# RS232-TTL.net
KiCad netlist of a schematic drawn in EAGLE
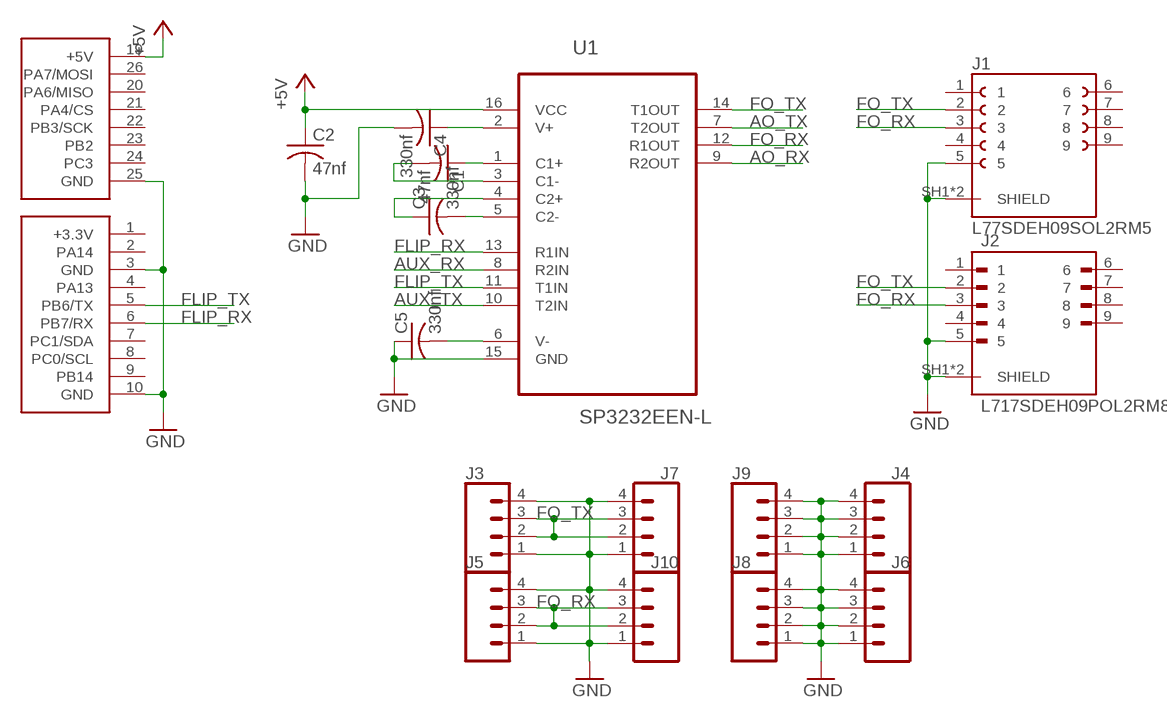
[diagram p0: schematic, sheet 1]

(export (version "E")
  (design (tool "Eeschema 10.0.6"))
  (components
    (comp (ref "C1")
      (value "47nf")
      (footprint "eagle-import:C0805")
      (libsource (lib "eagle-import") (part "C-USC0805"))
    )
    (comp (ref "C2")
      (value "47nf")
      (footprint "eagle-import:C0805")
      (libsource (lib "eagle-import") (part "C-USC0805"))
    )
    (comp (ref "C3")
      (value "330nf")
      (footprint "eagle-import:C0805")
      (libsource (lib "eagle-import") (part "C-USC0805"))
    )
    (comp (ref "C4")
      (value "330nf")
      (footprint "eagle-import:C0805")
      (libsource (lib "eagle-import") (part "C-USC0805"))
    )
    (comp (ref "C5")
      (value "330nf")
      (footprint "eagle-import:C0805")
      (libsource (lib "eagle-import") (part "C-USC0805"))
    )
    (comp (ref "J1")
      (value "L77SDEH09SOL2RM5")
      (footprint "eagle-import:AMPHENOL_L77SDEH09SOL2RM5")
      (fields (field (name "DIGIKEY_PART_NUMBER") "L77SDEH09SOL2RM5-ND") (field (name "MF") "Amphenol ICC"))
      (libsource (lib "eagle-import") (part "L77SDEH09SOL2RM5"))
    )
    (comp (ref "J2")
      (value "L717SDEH09POL2RM8")
      (footprint "eagle-import:AMPHENOL_L717SDEH09POL2RM8")
      (fields (field (name "DIGIKEY_PART_NUMBER") "L717SDEH09POL2RM8-ND") (field (name "MF") "Amphenol ICC"))
      (libsource (lib "eagle-import") (part "L717SDEH09POL2RM8"))
    )
    (comp (ref "J3")
      (value "CONN_04SMD_VERTICAL_MALE")
      (footprint "eagle-import:1X04_SMD_VERTICAL_COMBO_CENTERED")
      (libsource (lib "eagle-import") (part "CONN_04SMD_VERTICAL_MALE"))
    )
    (comp (ref "J4")
      (value "CONN_04SMD_VERTICAL_MALE")
      (footprint "eagle-import:1X04_SMD_VERTICAL_COMBO_CENTERED")
      (libsource (lib "eagle-import") (part "CONN_04SMD_VERTICAL_MALE"))
    )
    (comp (ref "J5")
      (value "CONN_04SMD_VERTICAL_MALE")
      (footprint "eagle-import:1X04_SMD_VERTICAL_COMBO_CENTERED")
      (libsource (lib "eagle-import") (part "CONN_04SMD_VERTICAL_MALE"))
    )
    (comp (ref "J6")
      (value "CONN_04SMD_VERTICAL_MALE")
      (footprint "eagle-import:1X04_SMD_VERTICAL_COMBO_CENTERED")
      (libsource (lib "eagle-import") (part "CONN_04SMD_VERTICAL_MALE"))
    )
    (comp (ref "J7")
      (value "CONN_04PTH")
      (footprint "eagle-import:1X04")
      (libsource (lib "eagle-import") (part "CONN_04PTH"))
    )
    (comp (ref "J8")
      (value "CONN_04PTH")
      (footprint "eagle-import:1X04")
      (libsource (lib "eagle-import") (part "CONN_04PTH"))
    )
    (comp (ref "J9")
      (value "CONN_04PTH")
      (footprint "eagle-import:1X04")
      (libsource (lib "eagle-import") (part "CONN_04PTH"))
    )
    (comp (ref "J10")
      (value "CONN_04PTH")
      (footprint "eagle-import:1X04")
      (libsource (lib "eagle-import") (part "CONN_04PTH"))
    )
    (comp (ref "U$1")
      (value "BOTH-SMD")
      (footprint "eagle-import:BOTH-SMD")
      (libsource (lib "eagle-import") (part "BOTH-SMD"))
    )
    (comp (ref "U1")
      (value "SP3232EEN-L")
      (footprint "eagle-import:SOIC127P600X175-16N")
      (fields (field (name "MF") "MaxLinear, Inc."))
      (libsource (lib "eagle-import") (part "SP3232EEN-L"))
    )
  )
  (nets
    (net (code "1") (name "+5V") (class "Default")
      (node (ref "C2") (pin "1") (pinfunction "1_1") (pintype "passive"))
      (node (ref "U$1") (pin "19") (pinfunction "+5V_19") (pintype "bidirectional"))
      (node (ref "U1") (pin "16") (pinfunction "VCC_16") (pintype "power_in"))
    )
    (net (code "2") (name "/AO_RX") (class "Default")
      (node (ref "U1") (pin "9") (pinfunction "R2OUT_9") (pintype "output"))
    )
    (net (code "3") (name "/AO_TX") (class "Default")
      (node (ref "U1") (pin "7") (pinfunction "T2OUT_7") (pintype "output"))
    )
    (net (code "4") (name "/AUX_RX") (class "Default")
      (node (ref "U1") (pin "8") (pinfunction "R2IN_8") (pintype "input"))
    )
    (net (code "5") (name "/AUX_TX") (class "Default")
      (node (ref "U1") (pin "10") (pinfunction "T2IN_10") (pintype "input"))
    )
    (net (code "6") (name "/FLIP_RX") (class "Default")
      (node (ref "U$1") (pin "6") (pinfunction "PB7/RX_6") (pintype "bidirectional"))
      (node (ref "U1") (pin "13") (pinfunction "R1IN_13") (pintype "input"))
    )
    (net (code "7") (name "/FLIP_TX") (class "Default")
      (node (ref "U$1") (pin "5") (pinfunction "PB6/TX_5") (pintype "bidirectional"))
      (node (ref "U1") (pin "11") (pinfunction "T1IN_11") (pintype "input"))
    )
    (net (code "8") (name "/FO_RX") (class "Default")
      (node (ref "J1") (pin "3") (pinfunction "3_3") (pintype "passive"))
      (node (ref "J10") (pin "2") (pinfunction "2_2") (pintype "passive"))
      (node (ref "J10") (pin "3") (pinfunction "3_3") (pintype "passive"))
      (node (ref "J2") (pin "3") (pinfunction "3_3") (pintype "passive"))
      (node (ref "J5") (pin "2") (pinfunction "2_2") (pintype "passive"))
      (node (ref "J5") (pin "3") (pinfunction "3_3") (pintype "passive"))
      (node (ref "U1") (pin "12") (pinfunction "R1OUT_12") (pintype "output"))
    )
    (net (code "9") (name "/FO_TX") (class "Default")
      (node (ref "J1") (pin "2") (pinfunction "2_2") (pintype "passive"))
      (node (ref "J2") (pin "2") (pinfunction "2_2") (pintype "passive"))
      (node (ref "J3") (pin "2") (pinfunction "2_2") (pintype "passive"))
      (node (ref "J3") (pin "3") (pinfunction "3_3") (pintype "passive"))
      (node (ref "J7") (pin "2") (pinfunction "2_2") (pintype "passive"))
      (node (ref "J7") (pin "3") (pinfunction "3_3") (pintype "passive"))
      (node (ref "U1") (pin "14") (pinfunction "T1OUT_14") (pintype "output"))
    )
    (net (code "10") (name "GND") (class "Default")
      (node (ref "C2") (pin "2") (pinfunction "2_2") (pintype "passive"))
      (node (ref "C4") (pin "2") (pinfunction "2_2") (pintype "passive"))
      (node (ref "C5") (pin "1") (pinfunction "1_1") (pintype "passive"))
      (node (ref "J1") (pin "5") (pinfunction "5_5") (pintype "passive"))
      (node (ref "J1") (pin "SH1") (pinfunction "SHIELD_SH1") (pintype "passive"))
      (node (ref "J1") (pin "SH2") (pinfunction "SHIELD_SH2") (pintype "passive"))
      (node (ref "J10") (pin "1") (pinfunction "1_1") (pintype "passive"))
      (node (ref "J10") (pin "4") (pinfunction "4_4") (pintype "passive"))
      (node (ref "J2") (pin "5") (pinfunction "5_5") (pintype "passive"))
      (node (ref "J2") (pin "SH1") (pinfunction "SHIELD_SH1") (pintype "passive"))
      (node (ref "J2") (pin "SH2") (pinfunction "SHIELD_SH2") (pintype "passive"))
      (node (ref "J3") (pin "1") (pinfunction "1_1") (pintype "passive"))
      (node (ref "J3") (pin "4") (pinfunction "4_4") (pintype "passive"))
      (node (ref "J4") (pin "1") (pinfunction "1_1") (pintype "passive"))
      (node (ref "J4") (pin "2") (pinfunction "2_2") (pintype "passive"))
      (node (ref "J4") (pin "3") (pinfunction "3_3") (pintype "passive"))
      (node (ref "J4") (pin "4") (pinfunction "4_4") (pintype "passive"))
      (node (ref "J5") (pin "1") (pinfunction "1_1") (pintype "passive"))
      (node (ref "J5") (pin "4") (pinfunction "4_4") (pintype "passive"))
      (node (ref "J6") (pin "1") (pinfunction "1_1") (pintype "passive"))
      (node (ref "J6") (pin "2") (pinfunction "2_2") (pintype "passive"))
      (node (ref "J6") (pin "3") (pinfunction "3_3") (pintype "passive"))
      (node (ref "J6") (pin "4") (pinfunction "4_4") (pintype "passive"))
      (node (ref "J7") (pin "1") (pinfunction "1_1") (pintype "passive"))
      (node (ref "J7") (pin "4") (pinfunction "4_4") (pintype "passive"))
      (node (ref "J8") (pin "1") (pinfunction "1_1") (pintype "passive"))
      (node (ref "J8") (pin "2") (pinfunction "2_2") (pintype "passive"))
      (node (ref "J8") (pin "3") (pinfunction "3_3") (pintype "passive"))
      (node (ref "J8") (pin "4") (pinfunction "4_4") (pintype "passive"))
      (node (ref "J9") (pin "1") (pinfunction "1_1") (pintype "passive"))
      (node (ref "J9") (pin "2") (pinfunction "2_2") (pintype "passive"))
      (node (ref "J9") (pin "3") (pinfunction "3_3") (pintype "passive"))
      (node (ref "J9") (pin "4") (pinfunction "4_4") (pintype "passive"))
      (node (ref "U$1") (pin "10") (pinfunction "GND_10") (pintype "bidirectional"))
      (node (ref "U$1") (pin "25") (pinfunction "GND_25") (pintype "bidirectional"))
      (node (ref "U$1") (pin "3") (pinfunction "GND_3") (pintype "bidirectional"))
      (node (ref "U1") (pin "15") (pinfunction "GND_15") (pintype "passive"))
    )
    (net (code "11") (name "Net-(U1-C1+)") (class "Default")
      (node (ref "C1") (pin "1") (pinfunction "1_1") (pintype "passive"))
      (node (ref "U1") (pin "1") (pinfunction "C1+_1") (pintype "passive"))
    )
    (net (code "12") (name "Net-(U1-C1-)") (class "Default")
      (node (ref "C1") (pin "2") (pinfunction "2_2") (pintype "passive"))
      (node (ref "U1") (pin "3") (pinfunction "C1-_3") (pintype "passive"))
    )
    (net (code "13") (name "Net-(U1-C2+)") (class "Default")
      (node (ref "C3") (pin "1") (pinfunction "1_1") (pintype "passive"))
      (node (ref "U1") (pin "4") (pinfunction "C2+_4") (pintype "passive"))
    )
    (net (code "14") (name "Net-(U1-C2-)") (class "Default")
      (node (ref "C3") (pin "2") (pinfunction "2_2") (pintype "passive"))
      (node (ref "U1") (pin "5") (pinfunction "C2-_5") (pintype "passive"))
    )
    (net (code "15") (name "Net-(U1-V+)") (class "Default")
      (node (ref "C4") (pin "1") (pinfunction "1_1") (pintype "passive"))
      (node (ref "U1") (pin "2") (pinfunction "V+_2") (pintype "power_in"))
    )
    (net (code "16") (name "Net-(U1-V-)") (class "Default")
      (node (ref "C5") (pin "2") (pinfunction "2_2") (pintype "passive"))
      (node (ref "U1") (pin "6") (pinfunction "V-_6") (pintype "power_in"))
    )
    (net (code "17") (name "unconnected-(J1-Pad1)") (class "Default")
      (node (ref "J1") (pin "1") (pinfunction "1_1") (pintype "passive"))
    )
    (net (code "18") (name "unconnected-(J1-Pad4)") (class "Default")
      (node (ref "J1") (pin "4") (pinfunction "4_4") (pintype "passive"))
    )
    (net (code "19") (name "unconnected-(J1-Pad6)") (class "Default")
      (node (ref "J1") (pin "6") (pinfunction "6_6") (pintype "passive"))
    )
    (net (code "20") (name "unconnected-(J1-Pad7)") (class "Default")
      (node (ref "J1") (pin "7") (pinfunction "7_7") (pintype "passive"))
    )
    (net (code "21") (name "unconnected-(J1-Pad8)") (class "Default")
      (node (ref "J1") (pin "8") (pinfunction "8_8") (pintype "passive"))
    )
    (net (code "22") (name "unconnected-(J1-Pad9)") (class "Default")
      (node (ref "J1") (pin "9") (pinfunction "9_9") (pintype "passive"))
    )
    (net (code "23") (name "unconnected-(J2-Pad1)") (class "Default")
      (node (ref "J2") (pin "1") (pinfunction "1_1") (pintype "passive"))
    )
    (net (code "24") (name "unconnected-(J2-Pad4)") (class "Default")
      (node (ref "J2") (pin "4") (pinfunction "4_4") (pintype "passive"))
    )
    (net (code "25") (name "unconnected-(J2-Pad6)") (class "Default")
      (node (ref "J2") (pin "6") (pinfunction "6_6") (pintype "passive"))
    )
    (net (code "26") (name "unconnected-(J2-Pad7)") (class "Default")
      (node (ref "J2") (pin "7") (pinfunction "7_7") (pintype "passive"))
    )
    (net (code "27") (name "unconnected-(J2-Pad8)") (class "Default")
      (node (ref "J2") (pin "8") (pinfunction "8_8") (pintype "passive"))
    )
    (net (code "28") (name "unconnected-(J2-Pad9)") (class "Default")
      (node (ref "J2") (pin "9") (pinfunction "9_9") (pintype "passive"))
    )
    (net (code "29") (name "unconnected-(U$1A-PA4{slash}CS-Pad21)") (class "Default")
      (node (ref "U$1") (pin "21") (pinfunction "PA4/CS_21") (pintype "bidirectional"))
    )
    (net (code "30") (name "unconnected-(U$1A-PA6{slash}MISO-Pad20)") (class "Default")
      (node (ref "U$1") (pin "20") (pinfunction "PA6/MISO_20") (pintype "bidirectional"))
    )
    (net (code "31") (name "unconnected-(U$1A-PA7{slash}MOSI-Pad26)") (class "Default")
      (node (ref "U$1") (pin "26") (pinfunction "PA7/MOSI_26") (pintype "bidirectional"))
    )
    (net (code "32") (name "unconnected-(U$1A-PB2-Pad23)") (class "Default")
      (node (ref "U$1") (pin "23") (pinfunction "PB2_23") (pintype "bidirectional"))
    )
    (net (code "33") (name "unconnected-(U$1A-PB3{slash}SCK-Pad22)") (class "Default")
      (node (ref "U$1") (pin "22") (pinfunction "PB3/SCK_22") (pintype "bidirectional"))
    )
    (net (code "34") (name "unconnected-(U$1A-PC3-Pad24)") (class "Default")
      (node (ref "U$1") (pin "24") (pinfunction "PC3_24") (pintype "bidirectional"))
    )
    (net (code "35") (name "unconnected-(U$1B-+3.3V-Pad1)") (class "Default")
      (node (ref "U$1") (pin "1") (pinfunction "+3.3V_1") (pintype "bidirectional"))
    )
    (net (code "36") (name "unconnected-(U$1B-PA13-Pad4)") (class "Default")
      (node (ref "U$1") (pin "4") (pinfunction "PA13_4") (pintype "bidirectional"))
    )
    (net (code "37") (name "unconnected-(U$1B-PA14-Pad2)") (class "Default")
      (node (ref "U$1") (pin "2") (pinfunction "PA14_2") (pintype "bidirectional"))
    )
    (net (code "38") (name "unconnected-(U$1B-PB14-Pad9)") (class "Default")
      (node (ref "U$1") (pin "9") (pinfunction "PB14_9") (pintype "bidirectional"))
    )
    (net (code "39") (name "unconnected-(U$1B-PC0{slash}SCL-Pad8)") (class "Default")
      (node (ref "U$1") (pin "8") (pinfunction "PC0/SCL_8") (pintype "bidirectional"))
    )
    (net (code "40") (name "unconnected-(U$1B-PC1{slash}SDA-Pad7)") (class "Default")
      (node (ref "U$1") (pin "7") (pinfunction "PC1/SDA_7") (pintype "bidirectional"))
    )
  )
)
